# SenzorDPCutie.net
KiCad netlist of a schematic drawn in EAGLE
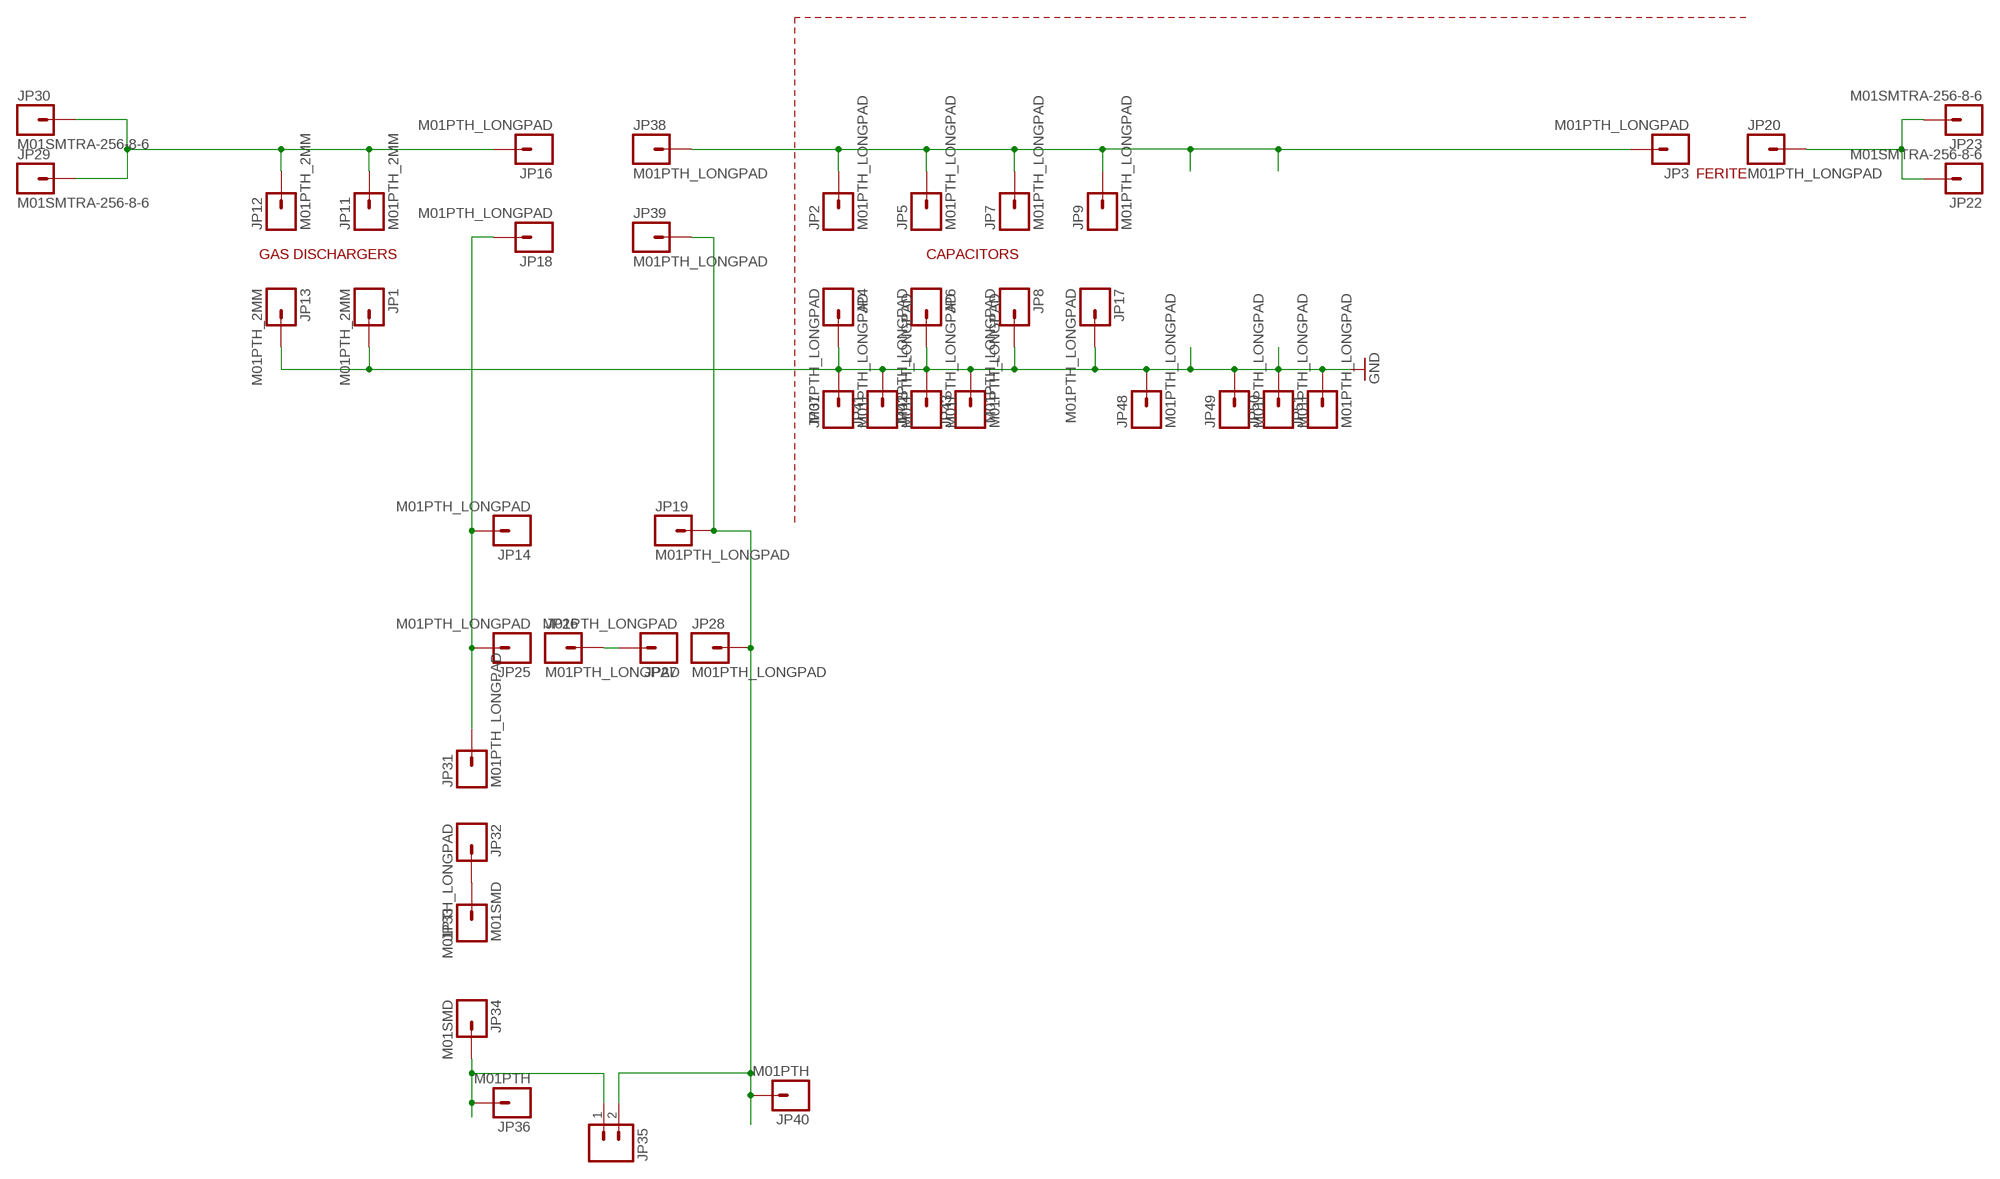
[diagram p0: schematic, sheet 1]

(export (version "E")
  (design (tool "Eeschema 10.0.6"))
  (components
    (comp (ref "JP1")
      (value "M01PTH_2MM")
      (footprint "eagle-import:1X01_2MM")
      (libsource (lib "eagle-import") (part "M01PTH_2MM"))
    )
    (comp (ref "JP2")
      (value "M01PTH_LONGPAD")
      (footprint "eagle-import:1X01_LONGPAD")
      (libsource (lib "eagle-import") (part "M01PTH_LONGPAD"))
    )
    (comp (ref "JP3")
      (value "M01PTH_LONGPAD")
      (footprint "eagle-import:1X01_LONGPAD")
      (libsource (lib "eagle-import") (part "M01PTH_LONGPAD"))
    )
    (comp (ref "JP4")
      (value "M01PTH_LONGPAD")
      (footprint "eagle-import:1X01_LONGPAD")
      (libsource (lib "eagle-import") (part "M01PTH_LONGPAD"))
    )
    (comp (ref "JP5")
      (value "M01PTH_LONGPAD")
      (footprint "eagle-import:1X01_LONGPAD")
      (libsource (lib "eagle-import") (part "M01PTH_LONGPAD"))
    )
    (comp (ref "JP6")
      (value "M01PTH_LONGPAD")
      (footprint "eagle-import:1X01_LONGPAD")
      (libsource (lib "eagle-import") (part "M01PTH_LONGPAD"))
    )
    (comp (ref "JP7")
      (value "M01PTH_LONGPAD")
      (footprint "eagle-import:1X01_LONGPAD")
      (libsource (lib "eagle-import") (part "M01PTH_LONGPAD"))
    )
    (comp (ref "JP8")
      (value "M01PTH_LONGPAD")
      (footprint "eagle-import:1X01_LONGPAD")
      (libsource (lib "eagle-import") (part "M01PTH_LONGPAD"))
    )
    (comp (ref "JP9")
      (value "M01PTH_LONGPAD")
      (footprint "eagle-import:1X01_LONGPAD")
      (libsource (lib "eagle-import") (part "M01PTH_LONGPAD"))
    )
    (comp (ref "JP11")
      (value "M01PTH_2MM")
      (footprint "eagle-import:1X01_2MM")
      (libsource (lib "eagle-import") (part "M01PTH_2MM"))
    )
    (comp (ref "JP12")
      (value "M01PTH_2MM")
      (footprint "eagle-import:1X01_2MM")
      (libsource (lib "eagle-import") (part "M01PTH_2MM"))
    )
    (comp (ref "JP13")
      (value "M01PTH_2MM")
      (footprint "eagle-import:1X01_2MM")
      (libsource (lib "eagle-import") (part "M01PTH_2MM"))
    )
    (comp (ref "JP14")
      (value "M01PTH_LONGPAD")
      (footprint "eagle-import:1X01_LONGPAD")
      (libsource (lib "eagle-import") (part "M01PTH_LONGPAD"))
    )
    (comp (ref "JP16")
      (value "M01PTH_LONGPAD")
      (footprint "eagle-import:1X01_LONGPAD")
      (libsource (lib "eagle-import") (part "M01PTH_LONGPAD"))
    )
    (comp (ref "JP17")
      (value "M01PTH_LONGPAD")
      (footprint "eagle-import:1X01_LONGPAD")
      (libsource (lib "eagle-import") (part "M01PTH_LONGPAD"))
    )
    (comp (ref "JP18")
      (value "M01PTH_LONGPAD")
      (footprint "eagle-import:1X01_LONGPAD")
      (libsource (lib "eagle-import") (part "M01PTH_LONGPAD"))
    )
    (comp (ref "JP19")
      (value "M01PTH_LONGPAD")
      (footprint "eagle-import:1X01_LONGPAD")
      (libsource (lib "eagle-import") (part "M01PTH_LONGPAD"))
    )
    (comp (ref "JP20")
      (value "M01PTH_LONGPAD")
      (footprint "eagle-import:1X01_LONGPAD")
      (libsource (lib "eagle-import") (part "M01PTH_LONGPAD"))
    )
    (comp (ref "JP22")
      (value "M01SMTRA-256-8-6")
      (footprint "eagle-import:SMTRA-256-8-6")
      (libsource (lib "eagle-import") (part "M01SMTRA-256-8-6"))
    )
    (comp (ref "JP23")
      (value "M01SMTRA-256-8-6")
      (footprint "eagle-import:SMTRA-256-8-6")
      (libsource (lib "eagle-import") (part "M01SMTRA-256-8-6"))
    )
    (comp (ref "JP25")
      (value "M01PTH_LONGPAD")
      (footprint "eagle-import:1X01_LONGPAD")
      (libsource (lib "eagle-import") (part "M01PTH_LONGPAD"))
    )
    (comp (ref "JP26")
      (value "M01PTH_LONGPAD")
      (footprint "eagle-import:1X01_LONGPAD")
      (libsource (lib "eagle-import") (part "M01PTH_LONGPAD"))
    )
    (comp (ref "JP27")
      (value "M01PTH_LONGPAD")
      (footprint "eagle-import:1X01_LONGPAD")
      (libsource (lib "eagle-import") (part "M01PTH_LONGPAD"))
    )
    (comp (ref "JP28")
      (value "M01PTH_LONGPAD")
      (footprint "eagle-import:1X01_LONGPAD")
      (libsource (lib "eagle-import") (part "M01PTH_LONGPAD"))
    )
    (comp (ref "JP29")
      (value "M01SMTRA-256-8-6")
      (footprint "eagle-import:SMTRA-256-8-6")
      (libsource (lib "eagle-import") (part "M01SMTRA-256-8-6"))
    )
    (comp (ref "JP30")
      (value "M01SMTRA-256-8-6")
      (footprint "eagle-import:SMTRA-256-8-6")
      (libsource (lib "eagle-import") (part "M01SMTRA-256-8-6"))
    )
    (comp (ref "JP31")
      (value "M01PTH_LONGPAD")
      (footprint "eagle-import:1X01_LONGPAD")
      (libsource (lib "eagle-import") (part "M01PTH_LONGPAD"))
    )
    (comp (ref "JP32")
      (value "M01PTH_LONGPAD")
      (footprint "eagle-import:1X01_LONGPAD")
      (libsource (lib "eagle-import") (part "M01PTH_LONGPAD"))
    )
    (comp (ref "JP33")
      (value "M01SMD")
      (footprint "eagle-import:LUXEON-PAD")
      (libsource (lib "eagle-import") (part "M01SMD"))
    )
    (comp (ref "JP34")
      (value "M01SMD")
      (footprint "eagle-import:LUXEON-PAD")
      (libsource (lib "eagle-import") (part "M01SMD"))
    )
    (comp (ref "JP35")
      (value "M025MM")
      (footprint "eagle-import:SCREWTERMINAL-5MM-2")
      (libsource (lib "eagle-import") (part "M025MM"))
    )
    (comp (ref "JP36")
      (value "M01PTH")
      (footprint "eagle-import:1X01")
      (libsource (lib "eagle-import") (part "M01PTH"))
    )
    (comp (ref "JP37")
      (value "M01PTH_LONGPAD")
      (footprint "eagle-import:1X01_LONGPAD")
      (libsource (lib "eagle-import") (part "M01PTH_LONGPAD"))
    )
    (comp (ref "JP38")
      (value "M01PTH_LONGPAD")
      (footprint "eagle-import:1X01_LONGPAD")
      (libsource (lib "eagle-import") (part "M01PTH_LONGPAD"))
    )
    (comp (ref "JP39")
      (value "M01PTH_LONGPAD")
      (footprint "eagle-import:1X01_LONGPAD")
      (libsource (lib "eagle-import") (part "M01PTH_LONGPAD"))
    )
    (comp (ref "JP40")
      (value "M01PTH")
      (footprint "eagle-import:1X01")
      (libsource (lib "eagle-import") (part "M01PTH"))
    )
    (comp (ref "JP41")
      (value "M01PTH_LONGPAD")
      (footprint "eagle-import:1X01_LONGPAD")
      (libsource (lib "eagle-import") (part "M01PTH_LONGPAD"))
    )
    (comp (ref "JP42")
      (value "M01PTH_LONGPAD")
      (footprint "eagle-import:1X01_LONGPAD")
      (libsource (lib "eagle-import") (part "M01PTH_LONGPAD"))
    )
    (comp (ref "JP43")
      (value "M01PTH_LONGPAD")
      (footprint "eagle-import:1X01_LONGPAD")
      (libsource (lib "eagle-import") (part "M01PTH_LONGPAD"))
    )
    (comp (ref "JP48")
      (value "M01PTH_LONGPAD")
      (footprint "eagle-import:1X01_LONGPAD")
      (libsource (lib "eagle-import") (part "M01PTH_LONGPAD"))
    )
    (comp (ref "JP49")
      (value "M01PTH_LONGPAD")
      (footprint "eagle-import:1X01_LONGPAD")
      (libsource (lib "eagle-import") (part "M01PTH_LONGPAD"))
    )
    (comp (ref "JP50")
      (value "M01PTH_LONGPAD")
      (footprint "eagle-import:1X01_LONGPAD")
      (libsource (lib "eagle-import") (part "M01PTH_LONGPAD"))
    )
    (comp (ref "JP51")
      (value "M01PTH_LONGPAD")
      (footprint "eagle-import:1X01_LONGPAD")
      (libsource (lib "eagle-import") (part "M01PTH_LONGPAD"))
    )
  )
  (nets
    (net (code "1") (name "GND") (class "Default")
      (node (ref "JP1") (pin "1") (pinfunction "1_1") (pintype "passive"))
      (node (ref "JP13") (pin "1") (pinfunction "1_1") (pintype "passive"))
      (node (ref "JP17") (pin "1") (pinfunction "1_1") (pintype "passive"))
      (node (ref "JP37") (pin "1") (pinfunction "1_1") (pintype "passive"))
      (node (ref "JP4") (pin "1") (pinfunction "1_1") (pintype "passive"))
      (node (ref "JP41") (pin "1") (pinfunction "1_1") (pintype "passive"))
      (node (ref "JP42") (pin "1") (pinfunction "1_1") (pintype "passive"))
      (node (ref "JP43") (pin "1") (pinfunction "1_1") (pintype "passive"))
      (node (ref "JP48") (pin "1") (pinfunction "1_1") (pintype "passive"))
      (node (ref "JP49") (pin "1") (pinfunction "1_1") (pintype "passive"))
      (node (ref "JP50") (pin "1") (pinfunction "1_1") (pintype "passive"))
      (node (ref "JP51") (pin "1") (pinfunction "1_1") (pintype "passive"))
      (node (ref "JP6") (pin "1") (pinfunction "1_1") (pintype "passive"))
      (node (ref "JP8") (pin "1") (pinfunction "1_1") (pintype "passive"))
    )
    (net (code "2") (name "Net-(JP2-Pad1)") (class "Default")
      (node (ref "JP2") (pin "1") (pinfunction "1_1") (pintype "passive"))
      (node (ref "JP3") (pin "1") (pinfunction "1_1") (pintype "passive"))
      (node (ref "JP38") (pin "1") (pinfunction "1_1") (pintype "passive"))
      (node (ref "JP5") (pin "1") (pinfunction "1_1") (pintype "passive"))
      (node (ref "JP7") (pin "1") (pinfunction "1_1") (pintype "passive"))
      (node (ref "JP9") (pin "1") (pinfunction "1_1") (pintype "passive"))
    )
    (net (code "3") (name "Net-(JP14-Pad1)") (class "Default")
      (node (ref "JP14") (pin "1") (pinfunction "1_1") (pintype "passive"))
      (node (ref "JP18") (pin "1") (pinfunction "1_1") (pintype "passive"))
      (node (ref "JP25") (pin "1") (pinfunction "1_1") (pintype "passive"))
      (node (ref "JP31") (pin "1") (pinfunction "1_1") (pintype "passive"))
    )
    (net (code "4") (name "Net-(JP19-Pad1)") (class "Default")
      (node (ref "JP19") (pin "1") (pinfunction "1_1") (pintype "passive"))
      (node (ref "JP28") (pin "1") (pinfunction "1_1") (pintype "passive"))
      (node (ref "JP35") (pin "2") (pinfunction "2_2") (pintype "passive"))
      (node (ref "JP39") (pin "1") (pinfunction "1_1") (pintype "passive"))
      (node (ref "JP40") (pin "1") (pinfunction "1_1") (pintype "passive"))
    )
    (net (code "5") (name "Net-(JP22-1)") (class "Default")
      (node (ref "JP20") (pin "1") (pinfunction "1_1") (pintype "passive"))
      (node (ref "JP22") (pin "P$1") (pinfunction "1_P$1") (pintype "passive"))
      (node (ref "JP23") (pin "P$1") (pinfunction "1_P$1") (pintype "passive"))
    )
    (net (code "6") (name "Net-(JP26-Pad1)") (class "Default")
      (node (ref "JP26") (pin "1") (pinfunction "1_1") (pintype "passive"))
      (node (ref "JP27") (pin "1") (pinfunction "1_1") (pintype "passive"))
    )
    (net (code "7") (name "Net-(JP29-1)") (class "Default")
      (node (ref "JP11") (pin "1") (pinfunction "1_1") (pintype "passive"))
      (node (ref "JP12") (pin "1") (pinfunction "1_1") (pintype "passive"))
      (node (ref "JP16") (pin "1") (pinfunction "1_1") (pintype "passive"))
      (node (ref "JP29") (pin "P$1") (pinfunction "1_P$1") (pintype "passive"))
      (node (ref "JP30") (pin "P$1") (pinfunction "1_P$1") (pintype "passive"))
    )
    (net (code "8") (name "Net-(JP33-1)") (class "Default")
      (node (ref "JP32") (pin "1") (pinfunction "1_1") (pintype "passive"))
      (node (ref "JP33") (pin "P$1") (pinfunction "1_P$1") (pintype "passive"))
    )
    (net (code "9") (name "Net-(JP34-1)") (class "Default")
      (node (ref "JP34") (pin "P$1") (pinfunction "1_P$1") (pintype "passive"))
      (node (ref "JP35") (pin "1") (pinfunction "1_1") (pintype "passive"))
      (node (ref "JP36") (pin "1") (pinfunction "1_1") (pintype "passive"))
    )
  )
)
